# WorkPart.net
KiCad netlist of a schematic drawn in Altium Designer
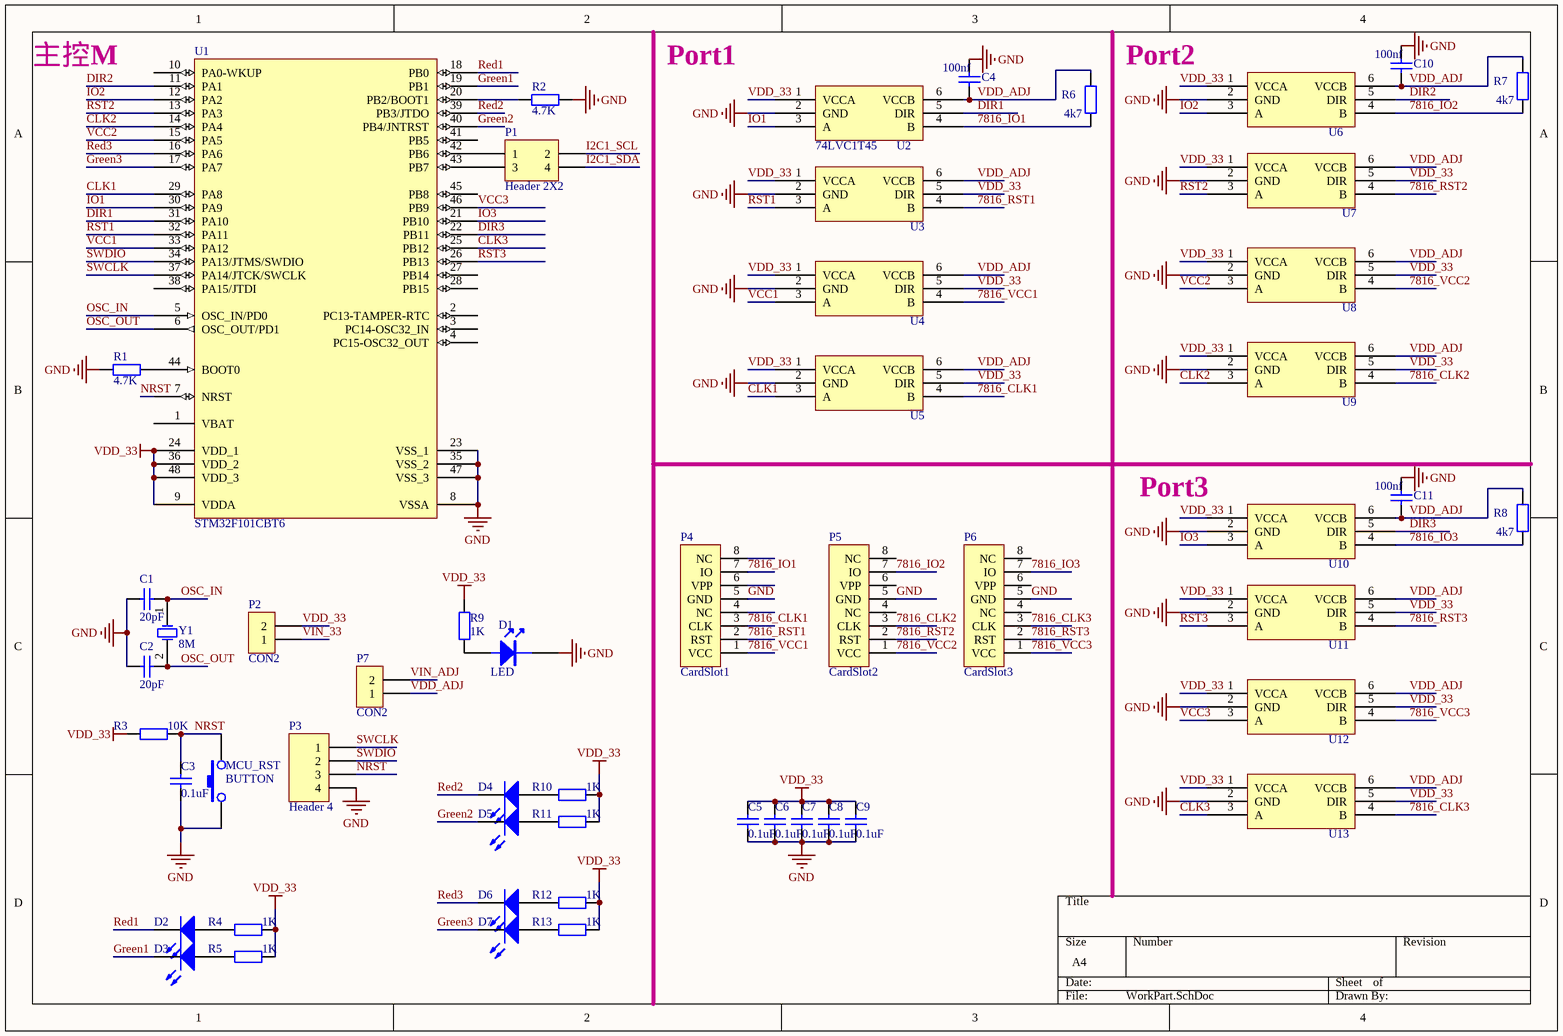
[diagram p0: WorkPart.SchDoc]

(export (version "E")
  (design (tool "Eeschema 10.0.6"))
  (components
    (comp (ref "C1")
      (value "20pF")
      (footprint "0805")
      (description "Capacitor")
      (fields (field (name "PUBLISHER") "Altium Limited"))
      (libsource (lib "Miscellaneous Devices") (part "Cap"))
    )
    (comp (ref "C2")
      (value "20pF")
      (footprint "0805")
      (description "Capacitor")
      (fields (field (name "PUBLISHER") "Altium Limited"))
      (libsource (lib "Miscellaneous Devices") (part "Cap"))
    )
    (comp (ref "C3")
      (value "0.1uF")
      (footprint "0805")
      (description "Capacitor")
      (fields (field (name "PUBLISHER") "Altium Limited"))
      (libsource (lib "Miscellaneous Devices") (part "Cap"))
    )
    (comp (ref "C4")
      (value "100nf")
      (footprint "0805")
      (description "0805贴片电容")
      (libsource (lib "通用元件库") (part "C"))
    )
    (comp (ref "C5")
      (value "0.1uF")
      (footprint "0805")
      (description "Capacitor")
      (fields (field (name "PUBLISHER") "Altium Limited"))
      (libsource (lib "Miscellaneous Devices") (part "Cap"))
    )
    (comp (ref "C6")
      (value "0.1uF")
      (footprint "0805")
      (description "Capacitor")
      (fields (field (name "PUBLISHER") "Altium Limited"))
      (libsource (lib "Miscellaneous Devices") (part "Cap"))
    )
    (comp (ref "C7")
      (value "0.1uF")
      (footprint "0805")
      (description "Capacitor")
      (fields (field (name "PUBLISHER") "Altium Limited"))
      (libsource (lib "Miscellaneous Devices") (part "Cap"))
    )
    (comp (ref "C8")
      (value "0.1uF")
      (footprint "0805")
      (description "Capacitor")
      (fields (field (name "PUBLISHER") "Altium Limited"))
      (libsource (lib "Miscellaneous Devices") (part "Cap"))
    )
    (comp (ref "C9")
      (value "0.1uF")
      (footprint "0805")
      (description "Capacitor")
      (fields (field (name "PUBLISHER") "Altium Limited"))
      (libsource (lib "Miscellaneous Devices") (part "Cap"))
    )
    (comp (ref "C10")
      (value "100nf")
      (footprint "0805")
      (description "0805贴片电容")
      (libsource (lib "通用元件库") (part "C"))
    )
    (comp (ref "C11")
      (value "100nf")
      (footprint "0805")
      (description "0805贴片电容")
      (libsource (lib "通用元件库") (part "C"))
    )
    (comp (ref "D1") (value "LED") (footprint "0805") (libsource (lib "FM_SCH") (part "LED")))
    (comp (ref "D2")
      (value "LED2")
      (footprint "0805")
      (description "Typical RED, GREEN, YELLOW, AMBER GaAs LED")
      (fields (field (name "PUBLISHER") "Altium Limited"))
      (libsource (lib "Miscellaneous Devices") (part "LED2"))
    )
    (comp (ref "D3")
      (value "LED2")
      (footprint "0805")
      (description "Typical RED, GREEN, YELLOW, AMBER GaAs LED")
      (fields (field (name "PUBLISHER") "Altium Limited"))
      (libsource (lib "Miscellaneous Devices") (part "LED2"))
    )
    (comp (ref "D4")
      (value "LED2")
      (footprint "0805")
      (description "Typical RED, GREEN, YELLOW, AMBER GaAs LED")
      (fields (field (name "PUBLISHER") "Altium Limited"))
      (libsource (lib "Miscellaneous Devices") (part "LED2"))
    )
    (comp (ref "D5")
      (value "LED2")
      (footprint "0805")
      (description "Typical RED, GREEN, YELLOW, AMBER GaAs LED")
      (fields (field (name "PUBLISHER") "Altium Limited"))
      (libsource (lib "Miscellaneous Devices") (part "LED2"))
    )
    (comp (ref "D6")
      (value "LED2")
      (footprint "0805")
      (description "Typical RED, GREEN, YELLOW, AMBER GaAs LED")
      (fields (field (name "PUBLISHER") "Altium Limited"))
      (libsource (lib "Miscellaneous Devices") (part "LED2"))
    )
    (comp (ref "D7")
      (value "LED2")
      (footprint "0805")
      (description "Typical RED, GREEN, YELLOW, AMBER GaAs LED")
      (fields (field (name "PUBLISHER") "Altium Limited"))
      (libsource (lib "Miscellaneous Devices") (part "LED2"))
    )
    (comp (ref "MCU_RST")
      (value "BUTTON")
      (footprint "BUTTON-S")
      (description "乒乓球按键（压下后接通，松开自动断开），较大按键尺寸12mmX12mm选用BUTTON-L封装，较小尺寸6mmX6mm选用BUTTON-S封装")
      (libsource (lib "fm274") (part "BUTTON"))
    )
    (comp (ref "P1")
      (value "Header 2X2")
      (footprint "HDR2X2")
      (description "Header, 2-Pin, Dual row")
      (fields (field (name "PUBLISHER") "Altium Limited"))
      (libsource (lib "Miscellaneous Connectors") (part "Header 2X2"))
    )
    (comp (ref "P2")
      (value "CON2")
      (footprint "SIP2")
      (description "Connector")
      (libsource (lib "YPF") (part "CON2"))
    )
    (comp (ref "P3")
      (value "Header 4")
      (footprint "SIP4")
      (description "Header, 4-Pin")
      (fields (field (name "PUBLISHER") "Altium Limited"))
      (libsource (lib "Miscellaneous Connectors") (part "Header 4"))
    )
    (comp (ref "P4") (value "CardSlot1") (footprint "CardSlot") (libsource (lib "Schlib1") (part "CardSlot")))
    (comp (ref "P5") (value "CardSlot2") (footprint "CardSlot") (libsource (lib "Schlib1") (part "CardSlot")))
    (comp (ref "P6") (value "CardSlot3") (footprint "CardSlot") (libsource (lib "Schlib1") (part "CardSlot")))
    (comp (ref "P7")
      (value "CON2")
      (footprint "SIP2")
      (description "Connector")
      (libsource (lib "YPF") (part "CON2"))
    )
    (comp (ref "R1")
      (value "4.7K")
      (footprint "0805")
      (description "0603")
      (libsource (lib "通用元件库") (part "R"))
    )
    (comp (ref "R2") (value "4.7K") (footprint "0805") (description "0603") (libsource (lib "") (part "R_1")))
    (comp (ref "R3")
      (value "10K")
      (footprint "0805")
      (description "Resistor")
      (fields (field (name "PUBLISHER") "Altium Limited"))
      (libsource (lib "") (part "Res2_1"))
    )
    (comp (ref "R4")
      (value "1K")
      (footprint "0805")
      (description "Resistor")
      (fields (field (name "PUBLISHER") "Altium Limited"))
      (libsource (lib "") (part "Res2_1"))
    )
    (comp (ref "R5")
      (value "1K")
      (footprint "0805")
      (description "Resistor")
      (fields (field (name "PUBLISHER") "Altium Limited"))
      (libsource (lib "Miscellaneous Devices") (part "Res2"))
    )
    (comp (ref "R6")
      (value "4k7")
      (footprint "0805")
      (description "0603")
      (libsource (lib "通用元件库") (part "R"))
    )
    (comp (ref "R7")
      (value "4k7")
      (footprint "0805")
      (description "0603")
      (libsource (lib "通用元件库") (part "R"))
    )
    (comp (ref "R8")
      (value "4k7")
      (footprint "0805")
      (description "0603")
      (libsource (lib "通用元件库") (part "R"))
    )
    (comp (ref "R9") (value "1K") (footprint "0805") (description "0805") (libsource (lib "") (part "R_2")))
    (comp (ref "R10")
      (value "1K")
      (footprint "0805")
      (description "Resistor")
      (fields (field (name "PUBLISHER") "Altium Limited"))
      (libsource (lib "") (part "Res2_1"))
    )
    (comp (ref "R11")
      (value "1K")
      (footprint "0805")
      (description "Resistor")
      (fields (field (name "PUBLISHER") "Altium Limited"))
      (libsource (lib "Miscellaneous Devices") (part "Res2"))
    )
    (comp (ref "R12")
      (value "1K")
      (footprint "0805")
      (description "Resistor")
      (fields (field (name "PUBLISHER") "Altium Limited"))
      (libsource (lib "") (part "Res2_1"))
    )
    (comp (ref "R13")
      (value "1K")
      (footprint "0805")
      (description "Resistor")
      (fields (field (name "PUBLISHER") "Altium Limited"))
      (libsource (lib "Miscellaneous Devices") (part "Res2"))
    )
    (comp (ref "U1")
      (value "STM32F101CBT6")
      (footprint "LQFP48_N")
      (description "STM32 ARM-based 32-bit MCU with 128 Kbytes Flash, 48-pin LQFP, Industrial Temperature")
      (fields (field (name "PUBLISHER") "Altium Limited"))
      (libsource (lib "YPF") (part "STM32F101CBT6"))
    )
    (comp (ref "U2")
      (value "74LVC1T45")
      (footprint "74LVC1T45")
      (libsource (lib "Schlib1") (part "74LVC1T45"))
    )
    (comp (ref "U3") (value "~") (footprint "74LVC1T45") (libsource (lib "Schlib1") (part "74LVC1T45")))
    (comp (ref "U4") (value "~") (footprint "74LVC1T45") (libsource (lib "Schlib1") (part "74LVC1T45")))
    (comp (ref "U5") (value "~") (footprint "74LVC1T45") (libsource (lib "Schlib1") (part "74LVC1T45")))
    (comp (ref "U6") (value "~") (footprint "74LVC1T45") (libsource (lib "Schlib1") (part "74LVC1T45")))
    (comp (ref "U7") (value "~") (footprint "74LVC1T45") (libsource (lib "Schlib1") (part "74LVC1T45")))
    (comp (ref "U8") (value "~") (footprint "74LVC1T45") (libsource (lib "Schlib1") (part "74LVC1T45")))
    (comp (ref "U9") (value "~") (footprint "74LVC1T45") (libsource (lib "Schlib1") (part "74LVC1T45")))
    (comp (ref "U10") (value "~") (footprint "74LVC1T45") (libsource (lib "Schlib1") (part "74LVC1T45")))
    (comp (ref "U11") (value "~") (footprint "74LVC1T45") (libsource (lib "Schlib1") (part "74LVC1T45")))
    (comp (ref "U12") (value "~") (footprint "74LVC1T45") (libsource (lib "Schlib1") (part "74LVC1T45")))
    (comp (ref "U13") (value "~") (footprint "74LVC1T45") (libsource (lib "Schlib1") (part "74LVC1T45")))
    (comp (ref "Y1")
      (value "8M")
      (footprint "XTAL-0.2")
      (description "Crystal Oscillator")
      (fields (field (name "PUBLISHER") "Altium Limited"))
      (libsource (lib "Miscellaneous Devices") (part "XTAL"))
    )
  )
  (nets
    (net (code "1") (name "/7816_CLK1") (class "Default")
      (node (ref "P4") (pin "3") (pinfunction "CLK_3") (pintype "passive"))
      (node (ref "U5") (pin "4") (pinfunction "B_4") (pintype "passive"))
    )
    (net (code "2") (name "/7816_CLK2") (class "Default")
      (node (ref "P5") (pin "3") (pinfunction "CLK_3") (pintype "passive"))
      (node (ref "U9") (pin "4") (pinfunction "B_4") (pintype "passive"))
    )
    (net (code "3") (name "/7816_CLK3") (class "Default")
      (node (ref "P6") (pin "3") (pinfunction "CLK_3") (pintype "passive"))
      (node (ref "U13") (pin "4") (pinfunction "B_4") (pintype "passive"))
    )
    (net (code "4") (name "/7816_IO1") (class "Default")
      (node (ref "P4") (pin "7") (pinfunction "IO_7") (pintype "passive"))
      (node (ref "R6") (pin "2") (pinfunction "2_2") (pintype "passive"))
      (node (ref "U2") (pin "4") (pinfunction "B_4") (pintype "passive"))
    )
    (net (code "5") (name "/7816_IO2") (class "Default")
      (node (ref "P5") (pin "7") (pinfunction "IO_7") (pintype "passive"))
      (node (ref "R7") (pin "2") (pinfunction "2_2") (pintype "passive"))
      (node (ref "U6") (pin "4") (pinfunction "B_4") (pintype "passive"))
    )
    (net (code "6") (name "/7816_IO3") (class "Default")
      (node (ref "P6") (pin "7") (pinfunction "IO_7") (pintype "passive"))
      (node (ref "R8") (pin "2") (pinfunction "2_2") (pintype "passive"))
      (node (ref "U10") (pin "4") (pinfunction "B_4") (pintype "passive"))
    )
    (net (code "7") (name "/7816_RST1") (class "Default")
      (node (ref "P4") (pin "2") (pinfunction "RST_2") (pintype "passive"))
      (node (ref "U3") (pin "4") (pinfunction "B_4") (pintype "passive"))
    )
    (net (code "8") (name "/7816_RST2") (class "Default")
      (node (ref "P5") (pin "2") (pinfunction "RST_2") (pintype "passive"))
      (node (ref "U7") (pin "4") (pinfunction "B_4") (pintype "passive"))
    )
    (net (code "9") (name "/7816_RST3") (class "Default")
      (node (ref "P6") (pin "2") (pinfunction "RST_2") (pintype "passive"))
      (node (ref "U11") (pin "4") (pinfunction "B_4") (pintype "passive"))
    )
    (net (code "10") (name "/7816_VCC1") (class "Default")
      (node (ref "P4") (pin "1") (pinfunction "VCC_1") (pintype "passive"))
      (node (ref "U4") (pin "4") (pinfunction "B_4") (pintype "passive"))
    )
    (net (code "11") (name "/7816_VCC2") (class "Default")
      (node (ref "P5") (pin "1") (pinfunction "VCC_1") (pintype "passive"))
      (node (ref "U8") (pin "4") (pinfunction "B_4") (pintype "passive"))
    )
    (net (code "12") (name "/7816_VCC3") (class "Default")
      (node (ref "P6") (pin "1") (pinfunction "VCC_1") (pintype "passive"))
      (node (ref "U12") (pin "4") (pinfunction "B_4") (pintype "passive"))
    )
    (net (code "13") (name "/CLK1") (class "Default")
      (node (ref "U1") (pin "29") (pinfunction "PA8_29") (pintype "bidirectional"))
      (node (ref "U5") (pin "3") (pinfunction "A_3") (pintype "passive"))
    )
    (net (code "14") (name "/CLK2") (class "Default")
      (node (ref "U1") (pin "14") (pinfunction "PA4_14") (pintype "bidirectional"))
      (node (ref "U9") (pin "3") (pinfunction "A_3") (pintype "passive"))
    )
    (net (code "15") (name "/CLK3") (class "Default")
      (node (ref "U1") (pin "25") (pinfunction "PB12_25") (pintype "bidirectional"))
      (node (ref "U13") (pin "3") (pinfunction "A_3") (pintype "passive"))
    )
    (net (code "16") (name "/DIR1") (class "Default")
      (node (ref "U1") (pin "31") (pinfunction "PA10_31") (pintype "bidirectional"))
      (node (ref "U2") (pin "5") (pinfunction "DIR_5") (pintype "passive"))
    )
    (net (code "17") (name "/DIR2") (class "Default")
      (node (ref "U1") (pin "11") (pinfunction "PA1_11") (pintype "bidirectional"))
      (node (ref "U6") (pin "5") (pinfunction "DIR_5") (pintype "passive"))
    )
    (net (code "18") (name "/DIR3") (class "Default")
      (node (ref "U1") (pin "22") (pinfunction "PB11_22") (pintype "bidirectional"))
      (node (ref "U10") (pin "5") (pinfunction "DIR_5") (pintype "passive"))
    )
    (net (code "19") (name "/Green1") (class "Default")
      (node (ref "D3") (pin "2") (pinfunction "K_2") (pintype "passive"))
      (node (ref "U1") (pin "19") (pinfunction "PB1_19") (pintype "bidirectional"))
    )
    (net (code "20") (name "/Green2") (class "Default")
      (node (ref "D5") (pin "2") (pinfunction "K_2") (pintype "passive"))
      (node (ref "U1") (pin "40") (pinfunction "PB4/JNTRST_40") (pintype "bidirectional"))
    )
    (net (code "21") (name "/Green3") (class "Default")
      (node (ref "D7") (pin "2") (pinfunction "K_2") (pintype "passive"))
      (node (ref "U1") (pin "17") (pinfunction "PA7_17") (pintype "bidirectional"))
    )
    (net (code "22") (name "/I2C1_SCL") (class "Default")
      (node (ref "P1") (pin "2") (pinfunction "2_2") (pintype "passive"))
    )
    (net (code "23") (name "/I2C1_SDA") (class "Default")
      (node (ref "P1") (pin "4") (pinfunction "4_4") (pintype "passive"))
    )
    (net (code "24") (name "/IO1") (class "Default")
      (node (ref "U1") (pin "30") (pinfunction "PA9_30") (pintype "bidirectional"))
      (node (ref "U2") (pin "3") (pinfunction "A_3") (pintype "passive"))
    )
    (net (code "25") (name "/IO2") (class "Default")
      (node (ref "U1") (pin "12") (pinfunction "PA2_12") (pintype "bidirectional"))
      (node (ref "U6") (pin "3") (pinfunction "A_3") (pintype "passive"))
    )
    (net (code "26") (name "/IO3") (class "Default")
      (node (ref "U1") (pin "21") (pinfunction "PB10_21") (pintype "bidirectional"))
      (node (ref "U10") (pin "3") (pinfunction "A_3") (pintype "passive"))
    )
    (net (code "27") (name "/NRST") (class "Default")
      (node (ref "C3") (pin "2") (pinfunction "2_2") (pintype "passive"))
      (node (ref "MCU_RST") (pin "2") (pinfunction "2_2") (pintype "passive"))
      (node (ref "P3") (pin "3") (pinfunction "3_3") (pintype "passive"))
      (node (ref "R3") (pin "2") (pinfunction "2_2") (pintype "passive"))
      (node (ref "U1") (pin "7") (pinfunction "NRST_7") (pintype "bidirectional"))
    )
    (net (code "28") (name "/OSC_IN") (class "Default")
      (node (ref "C1") (pin "1") (pinfunction "1_1") (pintype "passive"))
      (node (ref "U1") (pin "5") (pinfunction "OSC_IN/PD0_5") (pintype "input"))
      (node (ref "Y1") (pin "1") (pinfunction "OSC1_1") (pintype "passive"))
    )
    (net (code "29") (name "/OSC_OUT") (class "Default")
      (node (ref "C2") (pin "1") (pinfunction "1_1") (pintype "passive"))
      (node (ref "U1") (pin "6") (pinfunction "OSC_OUT/PD1_6") (pintype "output"))
      (node (ref "Y1") (pin "2") (pinfunction "OSC2_2") (pintype "passive"))
    )
    (net (code "30") (name "/RST1") (class "Default")
      (node (ref "U1") (pin "32") (pinfunction "PA11_32") (pintype "bidirectional"))
      (node (ref "U3") (pin "3") (pinfunction "A_3") (pintype "passive"))
    )
    (net (code "31") (name "/RST2") (class "Default")
      (node (ref "U1") (pin "13") (pinfunction "PA3_13") (pintype "bidirectional"))
      (node (ref "U7") (pin "3") (pinfunction "A_3") (pintype "passive"))
    )
    (net (code "32") (name "/RST3") (class "Default")
      (node (ref "U1") (pin "26") (pinfunction "PB13_26") (pintype "bidirectional"))
      (node (ref "U11") (pin "3") (pinfunction "A_3") (pintype "passive"))
    )
    (net (code "33") (name "/Red1") (class "Default")
      (node (ref "D2") (pin "2") (pinfunction "K_2") (pintype "passive"))
      (node (ref "U1") (pin "18") (pinfunction "PB0_18") (pintype "bidirectional"))
    )
    (net (code "34") (name "/Red2") (class "Default")
      (node (ref "D4") (pin "2") (pinfunction "K_2") (pintype "passive"))
      (node (ref "U1") (pin "39") (pinfunction "PB3/JTDO_39") (pintype "bidirectional"))
    )
    (net (code "35") (name "/Red3") (class "Default")
      (node (ref "D6") (pin "2") (pinfunction "K_2") (pintype "passive"))
      (node (ref "U1") (pin "16") (pinfunction "PA6_16") (pintype "bidirectional"))
    )
    (net (code "36") (name "/SWCLK") (class "Default")
      (node (ref "P3") (pin "1") (pinfunction "1_1") (pintype "passive"))
      (node (ref "U1") (pin "37") (pinfunction "PA14/JTCK/SWCLK_37") (pintype "bidirectional"))
    )
    (net (code "37") (name "/SWDIO") (class "Default")
      (node (ref "P3") (pin "2") (pinfunction "2_2") (pintype "passive"))
      (node (ref "U1") (pin "34") (pinfunction "PA13/JTMS/SWDIO_34") (pintype "bidirectional"))
    )
    (net (code "38") (name "/VCC1") (class "Default")
      (node (ref "U1") (pin "33") (pinfunction "PA12_33") (pintype "bidirectional"))
      (node (ref "U4") (pin "3") (pinfunction "A_3") (pintype "passive"))
    )
    (net (code "39") (name "/VCC2") (class "Default")
      (node (ref "U1") (pin "15") (pinfunction "PA5_15") (pintype "bidirectional"))
      (node (ref "U8") (pin "3") (pinfunction "A_3") (pintype "passive"))
    )
    (net (code "40") (name "/VCC3") (class "Default")
      (node (ref "U1") (pin "46") (pinfunction "PB9_46") (pintype "bidirectional"))
      (node (ref "U12") (pin "3") (pinfunction "A_3") (pintype "passive"))
    )
    (net (code "41") (name "/VDD_ADJ") (class "Default")
      (node (ref "C10") (pin "2") (pinfunction "2_2") (pintype "passive"))
      (node (ref "C11") (pin "2") (pinfunction "2_2") (pintype "passive"))
      (node (ref "C4") (pin "2") (pinfunction "2_2") (pintype "passive"))
      (node (ref "P7") (pin "1") (pinfunction "1_1") (pintype "passive"))
      (node (ref "R6") (pin "1") (pinfunction "1_1") (pintype "passive"))
      (node (ref "R7") (pin "1") (pinfunction "1_1") (pintype "passive"))
      (node (ref "R8") (pin "1") (pinfunction "1_1") (pintype "passive"))
      (node (ref "U10") (pin "6") (pinfunction "VCCB_6") (pintype "passive"))
      (node (ref "U11") (pin "6") (pinfunction "VCCB_6") (pintype "passive"))
      (node (ref "U12") (pin "6") (pinfunction "VCCB_6") (pintype "passive"))
      (node (ref "U13") (pin "6") (pinfunction "VCCB_6") (pintype "passive"))
      (node (ref "U2") (pin "6") (pinfunction "VCCB_6") (pintype "passive"))
      (node (ref "U3") (pin "6") (pinfunction "VCCB_6") (pintype "passive"))
      (node (ref "U4") (pin "6") (pinfunction "VCCB_6") (pintype "passive"))
      (node (ref "U5") (pin "6") (pinfunction "VCCB_6") (pintype "passive"))
      (node (ref "U6") (pin "6") (pinfunction "VCCB_6") (pintype "passive"))
      (node (ref "U7") (pin "6") (pinfunction "VCCB_6") (pintype "passive"))
      (node (ref "U8") (pin "6") (pinfunction "VCCB_6") (pintype "passive"))
      (node (ref "U9") (pin "6") (pinfunction "VCCB_6") (pintype "passive"))
    )
    (net (code "42") (name "/VIN_33") (class "Default")
      (node (ref "P2") (pin "1") (pinfunction "1_1") (pintype "passive"))
    )
    (net (code "43") (name "/VIN_ADJ") (class "Default")
      (node (ref "P7") (pin "2") (pinfunction "2_2") (pintype "passive"))
    )
    (net (code "44") (name "GND") (class "Default")
      (node (ref "C1") (pin "2") (pinfunction "2_2") (pintype "passive"))
      (node (ref "C10") (pin "1") (pinfunction "1_1") (pintype "passive"))
      (node (ref "C11") (pin "1") (pinfunction "1_1") (pintype "passive"))
      (node (ref "C2") (pin "2") (pinfunction "2_2") (pintype "passive"))
      (node (ref "C3") (pin "1") (pinfunction "1_1") (pintype "passive"))
      (node (ref "C4") (pin "1") (pinfunction "1_1") (pintype "passive"))
      (node (ref "C5") (pin "1") (pinfunction "1_1") (pintype "passive"))
      (node (ref "C6") (pin "1") (pinfunction "1_1") (pintype "passive"))
      (node (ref "C7") (pin "1") (pinfunction "1_1") (pintype "passive"))
      (node (ref "C8") (pin "1") (pinfunction "1_1") (pintype "passive"))
      (node (ref "C9") (pin "1") (pinfunction "1_1") (pintype "passive"))
      (node (ref "D1") (pin "2") (pinfunction "K_2") (pintype "passive"))
      (node (ref "MCU_RST") (pin "1") (pinfunction "1_1") (pintype "passive"))
      (node (ref "P3") (pin "4") (pinfunction "4_4") (pintype "passive"))
      (node (ref "P4") (pin "5") (pinfunction "GND_5") (pintype "passive"))
      (node (ref "P5") (pin "5") (pinfunction "GND_5") (pintype "passive"))
      (node (ref "P6") (pin "5") (pinfunction "GND_5") (pintype "passive"))
      (node (ref "R1") (pin "2") (pinfunction "2_2") (pintype "passive"))
      (node (ref "R2") (pin "2") (pinfunction "2_2") (pintype "passive"))
      (node (ref "U1") (pin "23") (pinfunction "VSS_1_23") (pintype "power_in"))
      (node (ref "U1") (pin "35") (pinfunction "VSS_2_35") (pintype "power_in"))
      (node (ref "U1") (pin "47") (pinfunction "VSS_3_47") (pintype "power_in"))
      (node (ref "U1") (pin "8") (pinfunction "VSSA_8") (pintype "power_in"))
      (node (ref "U10") (pin "2") (pinfunction "GND_2") (pintype "passive"))
      (node (ref "U11") (pin "2") (pinfunction "GND_2") (pintype "passive"))
      (node (ref "U12") (pin "2") (pinfunction "GND_2") (pintype "passive"))
      (node (ref "U13") (pin "2") (pinfunction "GND_2") (pintype "passive"))
      (node (ref "U2") (pin "2") (pinfunction "GND_2") (pintype "passive"))
      (node (ref "U3") (pin "2") (pinfunction "GND_2") (pintype "passive"))
      (node (ref "U4") (pin "2") (pinfunction "GND_2") (pintype "passive"))
      (node (ref "U5") (pin "2") (pinfunction "GND_2") (pintype "passive"))
      (node (ref "U6") (pin "2") (pinfunction "GND_2") (pintype "passive"))
      (node (ref "U7") (pin "2") (pinfunction "GND_2") (pintype "passive"))
      (node (ref "U8") (pin "2") (pinfunction "GND_2") (pintype "passive"))
      (node (ref "U9") (pin "2") (pinfunction "GND_2") (pintype "passive"))
    )
    (net (code "45") (name "Net-(D1-A)") (class "Default")
      (node (ref "D1") (pin "1") (pinfunction "A_1") (pintype "passive"))
      (node (ref "R9") (pin "2") (pinfunction "2_2") (pintype "passive"))
    )
    (net (code "46") (name "Net-(D2-A)") (class "Default")
      (node (ref "D2") (pin "1") (pinfunction "A_1") (pintype "passive"))
      (node (ref "R4") (pin "1") (pinfunction "1_1") (pintype "passive"))
    )
    (net (code "47") (name "Net-(D3-A)") (class "Default")
      (node (ref "D3") (pin "1") (pinfunction "A_1") (pintype "passive"))
      (node (ref "R5") (pin "2") (pinfunction "2_2") (pintype "passive"))
    )
    (net (code "48") (name "Net-(D4-A)") (class "Default")
      (node (ref "D4") (pin "1") (pinfunction "A_1") (pintype "passive"))
      (node (ref "R10") (pin "1") (pinfunction "1_1") (pintype "passive"))
    )
    (net (code "49") (name "Net-(D5-A)") (class "Default")
      (node (ref "D5") (pin "1") (pinfunction "A_1") (pintype "passive"))
      (node (ref "R11") (pin "2") (pinfunction "2_2") (pintype "passive"))
    )
    (net (code "50") (name "Net-(D6-A)") (class "Default")
      (node (ref "D6") (pin "1") (pinfunction "A_1") (pintype "passive"))
      (node (ref "R12") (pin "1") (pinfunction "1_1") (pintype "passive"))
    )
    (net (code "51") (name "Net-(D7-A)") (class "Default")
      (node (ref "D7") (pin "1") (pinfunction "A_1") (pintype "passive"))
      (node (ref "R13") (pin "2") (pinfunction "2_2") (pintype "passive"))
    )
    (net (code "52") (name "Net-(U1-BOOT0)") (class "Default")
      (node (ref "R1") (pin "1") (pinfunction "1_1") (pintype "passive"))
      (node (ref "U1") (pin "44") (pinfunction "BOOT0_44") (pintype "input"))
    )
    (net (code "53") (name "Net-(U1-PB2{slash}BOOT1)") (class "Default")
      (node (ref "R2") (pin "1") (pinfunction "1_1") (pintype "passive"))
      (node (ref "U1") (pin "20") (pinfunction "PB2/BOOT1_20") (pintype "bidirectional"))
    )
    (net (code "54") (name "Net-(U1-PB6)") (class "Default")
      (node (ref "P1") (pin "1") (pinfunction "1_1") (pintype "passive"))
      (node (ref "U1") (pin "42") (pinfunction "PB6_42") (pintype "bidirectional"))
    )
    (net (code "55") (name "Net-(U1-PB7)") (class "Default")
      (node (ref "P1") (pin "3") (pinfunction "3_3") (pintype "passive"))
      (node (ref "U1") (pin "43") (pinfunction "PB7_43") (pintype "bidirectional"))
    )
    (net (code "56") (name "VDD_33") (class "Default")
      (node (ref "C5") (pin "2") (pinfunction "2_2") (pintype "passive"))
      (node (ref "C6") (pin "2") (pinfunction "2_2") (pintype "passive"))
      (node (ref "C7") (pin "2") (pinfunction "2_2") (pintype "passive"))
      (node (ref "C8") (pin "2") (pinfunction "2_2") (pintype "passive"))
      (node (ref "C9") (pin "2") (pinfunction "2_2") (pintype "passive"))
      (node (ref "P2") (pin "2") (pinfunction "2_2") (pintype "passive"))
      (node (ref "R10") (pin "2") (pinfunction "2_2") (pintype "passive"))
      (node (ref "R11") (pin "1") (pinfunction "1_1") (pintype "passive"))
      (node (ref "R12") (pin "2") (pinfunction "2_2") (pintype "passive"))
      (node (ref "R13") (pin "1") (pinfunction "1_1") (pintype "passive"))
      (node (ref "R3") (pin "1") (pinfunction "1_1") (pintype "passive"))
      (node (ref "R4") (pin "2") (pinfunction "2_2") (pintype "passive"))
      (node (ref "R5") (pin "1") (pinfunction "1_1") (pintype "passive"))
      (node (ref "R9") (pin "1") (pinfunction "1_1") (pintype "passive"))
      (node (ref "U1") (pin "24") (pinfunction "VDD_1_24") (pintype "power_in"))
      (node (ref "U1") (pin "36") (pinfunction "VDD_2_36") (pintype "power_in"))
      (node (ref "U1") (pin "48") (pinfunction "VDD_3_48") (pintype "power_in"))
      (node (ref "U1") (pin "9") (pinfunction "VDDA_9") (pintype "power_in"))
      (node (ref "U10") (pin "1") (pinfunction "VCCA_1") (pintype "passive"))
      (node (ref "U11") (pin "1") (pinfunction "VCCA_1") (pintype "passive"))
      (node (ref "U11") (pin "5") (pinfunction "DIR_5") (pintype "passive"))
      (node (ref "U12") (pin "1") (pinfunction "VCCA_1") (pintype "passive"))
      (node (ref "U12") (pin "5") (pinfunction "DIR_5") (pintype "passive"))
      (node (ref "U13") (pin "1") (pinfunction "VCCA_1") (pintype "passive"))
      (node (ref "U13") (pin "5") (pinfunction "DIR_5") (pintype "passive"))
      (node (ref "U2") (pin "1") (pinfunction "VCCA_1") (pintype "passive"))
      (node (ref "U3") (pin "1") (pinfunction "VCCA_1") (pintype "passive"))
      (node (ref "U3") (pin "5") (pinfunction "DIR_5") (pintype "passive"))
      (node (ref "U4") (pin "1") (pinfunction "VCCA_1") (pintype "passive"))
      (node (ref "U4") (pin "5") (pinfunction "DIR_5") (pintype "passive"))
      (node (ref "U5") (pin "1") (pinfunction "VCCA_1") (pintype "passive"))
      (node (ref "U5") (pin "5") (pinfunction "DIR_5") (pintype "passive"))
      (node (ref "U6") (pin "1") (pinfunction "VCCA_1") (pintype "passive"))
      (node (ref "U7") (pin "1") (pinfunction "VCCA_1") (pintype "passive"))
      (node (ref "U7") (pin "5") (pinfunction "DIR_5") (pintype "passive"))
      (node (ref "U8") (pin "1") (pinfunction "VCCA_1") (pintype "passive"))
      (node (ref "U8") (pin "5") (pinfunction "DIR_5") (pintype "passive"))
      (node (ref "U9") (pin "1") (pinfunction "VCCA_1") (pintype "passive"))
      (node (ref "U9") (pin "5") (pinfunction "DIR_5") (pintype "passive"))
    )
    (net (code "57") (name "unconnected-(P4-NC-Pad4)") (class "Default")
      (node (ref "P4") (pin "4") (pinfunction "NC_4") (pintype "passive"))
    )
    (net (code "58") (name "unconnected-(P4-NC-Pad8)") (class "Default")
      (node (ref "P4") (pin "8") (pinfunction "NC_8") (pintype "passive"))
    )
    (net (code "59") (name "unconnected-(P4-VPP-Pad6)") (class "Default")
      (node (ref "P4") (pin "6") (pinfunction "VPP_6") (pintype "passive"))
    )
    (net (code "60") (name "unconnected-(P5-NC-Pad4)") (class "Default")
      (node (ref "P5") (pin "4") (pinfunction "NC_4") (pintype "passive"))
    )
    (net (code "61") (name "unconnected-(P5-NC-Pad8)") (class "Default")
      (node (ref "P5") (pin "8") (pinfunction "NC_8") (pintype "passive"))
    )
    (net (code "62") (name "unconnected-(P5-VPP-Pad6)") (class "Default")
      (node (ref "P5") (pin "6") (pinfunction "VPP_6") (pintype "passive"))
    )
    (net (code "63") (name "unconnected-(P6-NC-Pad4)") (class "Default")
      (node (ref "P6") (pin "4") (pinfunction "NC_4") (pintype "passive"))
    )
    (net (code "64") (name "unconnected-(P6-NC-Pad8)") (class "Default")
      (node (ref "P6") (pin "8") (pinfunction "NC_8") (pintype "passive"))
    )
    (net (code "65") (name "unconnected-(P6-VPP-Pad6)") (class "Default")
      (node (ref "P6") (pin "6") (pinfunction "VPP_6") (pintype "passive"))
    )
    (net (code "66") (name "unconnected-(U1-PA0-WKUP-Pad10)") (class "Default")
      (node (ref "U1") (pin "10") (pinfunction "PA0-WKUP_10") (pintype "bidirectional"))
    )
    (net (code "67") (name "unconnected-(U1-PA15{slash}JTDI-Pad38)") (class "Default")
      (node (ref "U1") (pin "38") (pinfunction "PA15/JTDI_38") (pintype "bidirectional"))
    )
    (net (code "68") (name "unconnected-(U1-PB5-Pad41)") (class "Default")
      (node (ref "U1") (pin "41") (pinfunction "PB5_41") (pintype "bidirectional"))
    )
    (net (code "69") (name "unconnected-(U1-PB8-Pad45)") (class "Default")
      (node (ref "U1") (pin "45") (pinfunction "PB8_45") (pintype "bidirectional"))
    )
    (net (code "70") (name "unconnected-(U1-PB14-Pad27)") (class "Default")
      (node (ref "U1") (pin "27") (pinfunction "PB14_27") (pintype "bidirectional"))
    )
    (net (code "71") (name "unconnected-(U1-PB15-Pad28)") (class "Default")
      (node (ref "U1") (pin "28") (pinfunction "PB15_28") (pintype "bidirectional"))
    )
    (net (code "72") (name "unconnected-(U1-PC13-TAMPER-RTC-Pad2)") (class "Default")
      (node (ref "U1") (pin "2") (pinfunction "PC13-TAMPER-RTC_2") (pintype "bidirectional"))
    )
    (net (code "73") (name "unconnected-(U1-PC14-OSC32_IN-Pad3)") (class "Default")
      (node (ref "U1") (pin "3") (pinfunction "PC14-OSC32_IN_3") (pintype "bidirectional"))
    )
    (net (code "74") (name "unconnected-(U1-PC15-OSC32_OUT-Pad4)") (class "Default")
      (node (ref "U1") (pin "4") (pinfunction "PC15-OSC32_OUT_4") (pintype "bidirectional"))
    )
    (net (code "75") (name "unconnected-(U1-VBAT-Pad1)") (class "Default")
      (node (ref "U1") (pin "1") (pinfunction "VBAT_1") (pintype "power_in"))
    )
  )
)
